# uven2-mk3-cc-interface.net
KiCad netlist of a schematic drawn in EasyEDA Pro
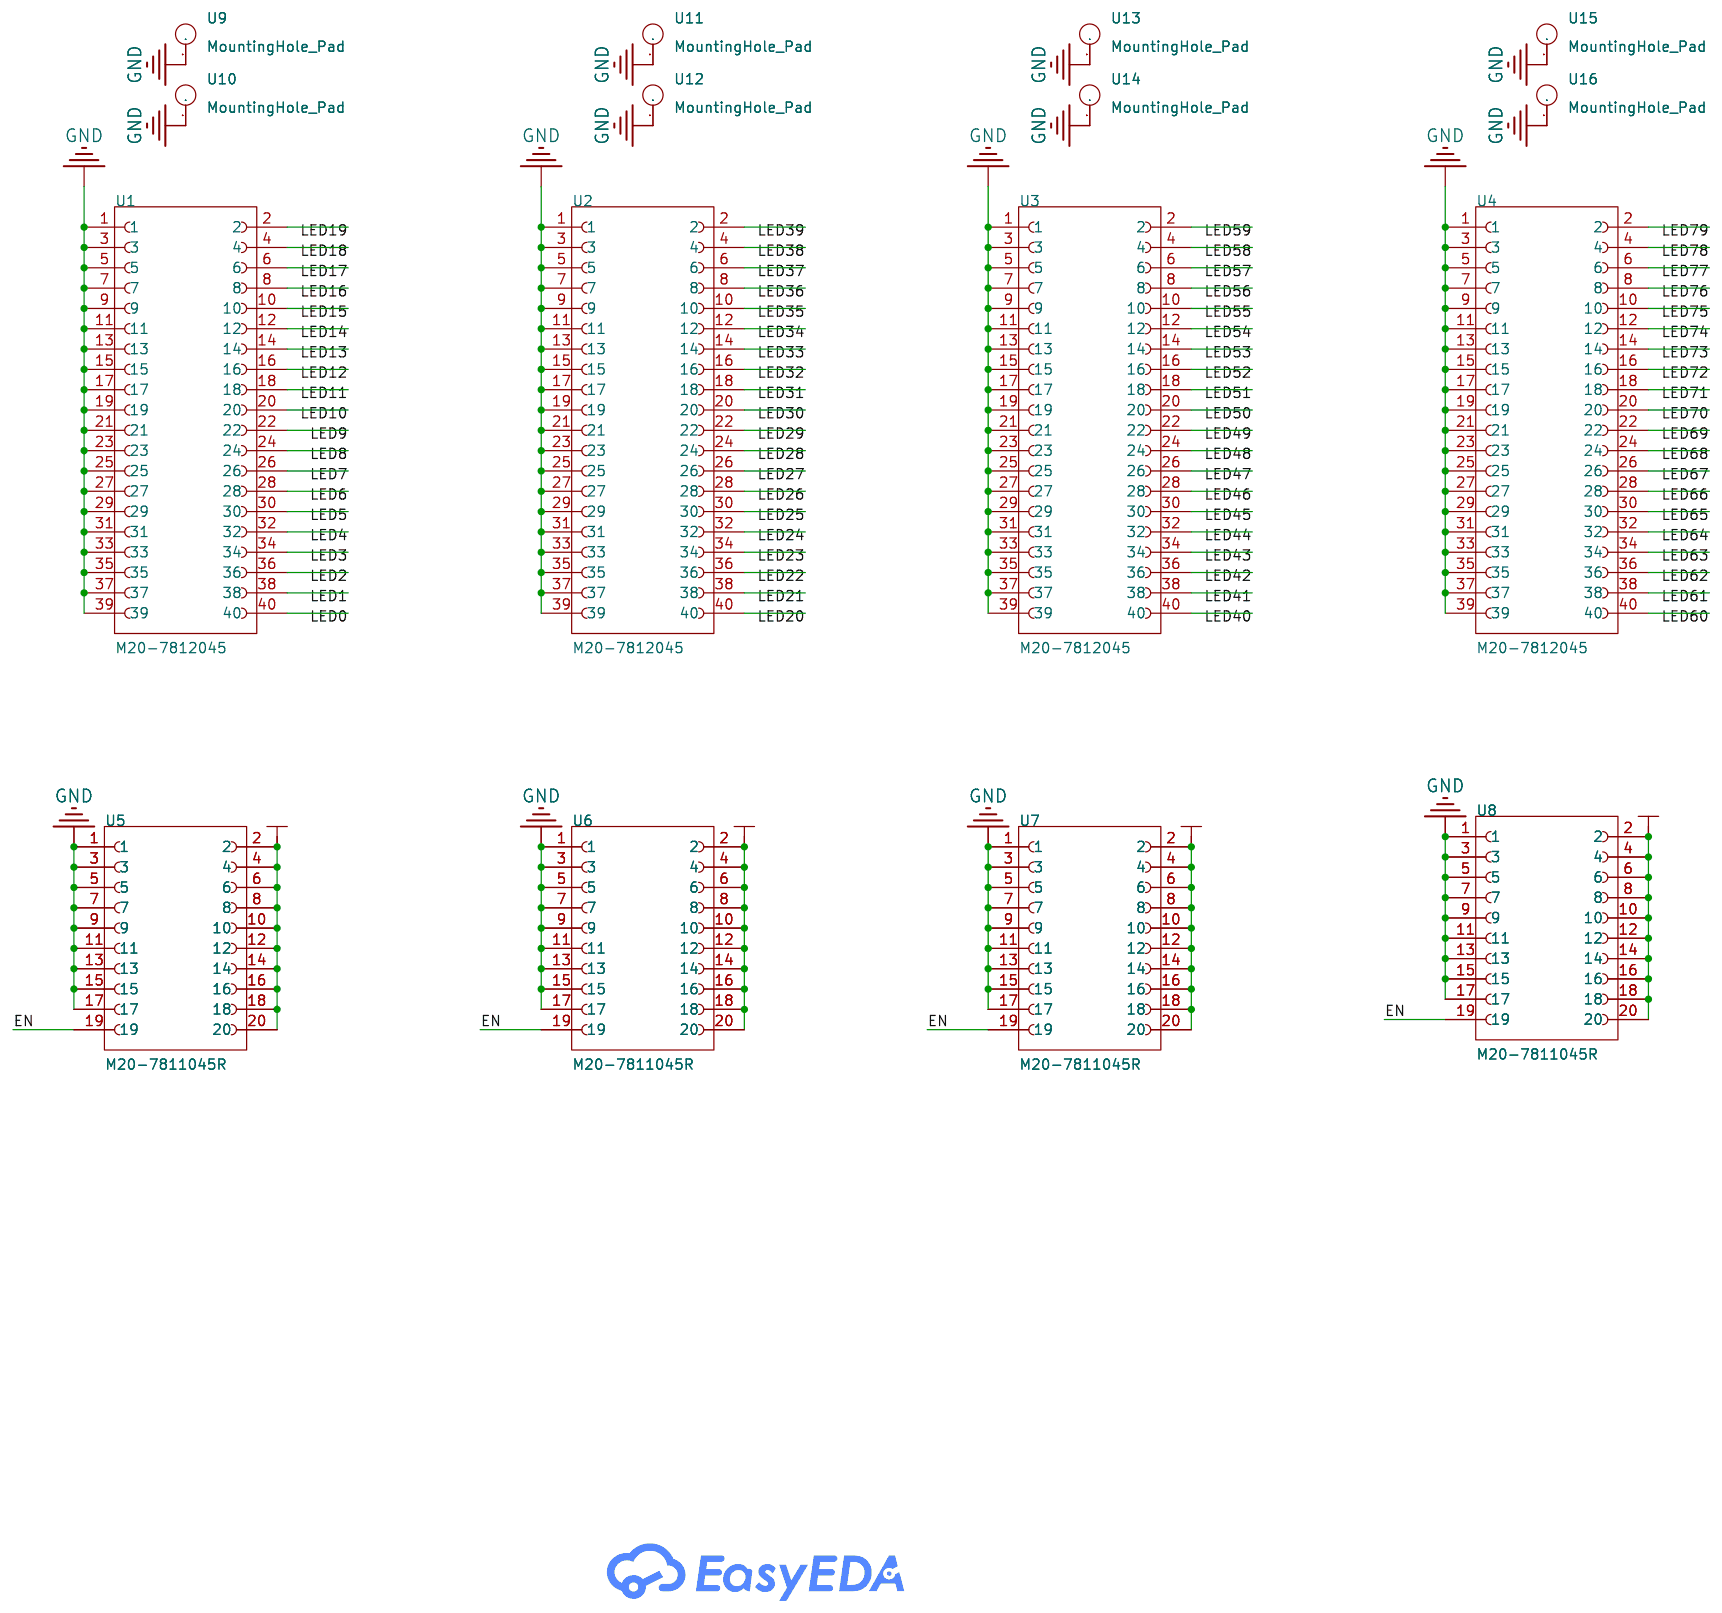
[diagram p0: schematic sheet]

(export (version "E")
  (design (tool "Eeschema 10.0.6"))
  (components
    (comp (ref "U1")
      (value "M20-7812045")
      (footprint "easyedapro:HARWIN_M20-7812045")
      (libsource (lib "easyedapro") (part "M20-7812045"))
    )
    (comp (ref "U2")
      (value "M20-7812045")
      (footprint "easyedapro:HARWIN_M20-7812045")
      (libsource (lib "easyedapro") (part "M20-7812045"))
    )
    (comp (ref "U3")
      (value "M20-7812045")
      (footprint "easyedapro:HARWIN_M20-7812045")
      (libsource (lib "easyedapro") (part "M20-7812045"))
    )
    (comp (ref "U4")
      (value "M20-7812045")
      (footprint "easyedapro:HARWIN_M20-7812045")
      (libsource (lib "easyedapro") (part "M20-7812045"))
    )
    (comp (ref "U5")
      (value "M20-7811045R")
      (footprint "easyedapro:HARWIN_M20-7811045R")
      (libsource (lib "easyedapro") (part "M20-7811045R"))
    )
    (comp (ref "U6")
      (value "M20-7811045R")
      (footprint "easyedapro:HARWIN_M20-7811045R")
      (libsource (lib "easyedapro") (part "M20-7811045R"))
    )
    (comp (ref "U7")
      (value "M20-7811045R")
      (footprint "easyedapro:HARWIN_M20-7811045R")
      (libsource (lib "easyedapro") (part "M20-7811045R"))
    )
    (comp (ref "U8")
      (value "M20-7811045R")
      (footprint "easyedapro:HARWIN_M20-7811045R")
      (libsource (lib "easyedapro") (part "M20-7811045R"))
    )
    (comp (ref "U9")
      (value "MountingHole_Pad")
      (footprint "easyedapro:MountingHole_3.2mm_M3_DIN965_Pad_TopOnly")
      (libsource (lib "easyedapro") (part "MountingHole_Pad"))
    )
    (comp (ref "U10")
      (value "MountingHole_Pad")
      (footprint "easyedapro:MountingHole_3.2mm_M3_DIN965_Pad_TopOnly")
      (libsource (lib "easyedapro") (part "MountingHole_Pad"))
    )
    (comp (ref "U11")
      (value "MountingHole_Pad")
      (footprint "easyedapro:MountingHole_3.2mm_M3_DIN965_Pad_TopOnly")
      (libsource (lib "easyedapro") (part "MountingHole_Pad"))
    )
    (comp (ref "U12")
      (value "MountingHole_Pad")
      (footprint "easyedapro:MountingHole_3.2mm_M3_DIN965_Pad_TopOnly")
      (libsource (lib "easyedapro") (part "MountingHole_Pad"))
    )
    (comp (ref "U13")
      (value "MountingHole_Pad")
      (footprint "easyedapro:MountingHole_3.2mm_M3_DIN965_Pad_TopOnly")
      (libsource (lib "easyedapro") (part "MountingHole_Pad"))
    )
    (comp (ref "U14")
      (value "MountingHole_Pad")
      (footprint "easyedapro:MountingHole_3.2mm_M3_DIN965_Pad_TopOnly")
      (libsource (lib "easyedapro") (part "MountingHole_Pad"))
    )
    (comp (ref "U15")
      (value "MountingHole_Pad")
      (footprint "easyedapro:MountingHole_3.2mm_M3_DIN965_Pad_TopOnly")
      (libsource (lib "easyedapro") (part "MountingHole_Pad"))
    )
    (comp (ref "U16")
      (value "MountingHole_Pad")
      (footprint "easyedapro:MountingHole_3.2mm_M3_DIN965_Pad_TopOnly")
      (libsource (lib "easyedapro") (part "MountingHole_Pad"))
    )
  )
  (nets
    (net (code "1") (name "+12V") (class "Default")
      (node (ref "U5") (pin "10") (pinfunction "10_10") (pintype "unspecified"))
      (node (ref "U5") (pin "12") (pinfunction "12_12") (pintype "unspecified"))
      (node (ref "U5") (pin "14") (pinfunction "14_14") (pintype "unspecified"))
      (node (ref "U5") (pin "16") (pinfunction "16_16") (pintype "unspecified"))
      (node (ref "U5") (pin "18") (pinfunction "18_18") (pintype "unspecified"))
      (node (ref "U5") (pin "2") (pinfunction "2_2") (pintype "unspecified"))
      (node (ref "U5") (pin "20") (pinfunction "20_20") (pintype "unspecified"))
      (node (ref "U5") (pin "4") (pinfunction "4_4") (pintype "unspecified"))
      (node (ref "U5") (pin "6") (pinfunction "6_6") (pintype "unspecified"))
      (node (ref "U5") (pin "8") (pinfunction "8_8") (pintype "unspecified"))
      (node (ref "U6") (pin "10") (pinfunction "10_10") (pintype "unspecified"))
      (node (ref "U6") (pin "12") (pinfunction "12_12") (pintype "unspecified"))
      (node (ref "U6") (pin "14") (pinfunction "14_14") (pintype "unspecified"))
      (node (ref "U6") (pin "16") (pinfunction "16_16") (pintype "unspecified"))
      (node (ref "U6") (pin "18") (pinfunction "18_18") (pintype "unspecified"))
      (node (ref "U6") (pin "2") (pinfunction "2_2") (pintype "unspecified"))
      (node (ref "U6") (pin "20") (pinfunction "20_20") (pintype "unspecified"))
      (node (ref "U6") (pin "4") (pinfunction "4_4") (pintype "unspecified"))
      (node (ref "U6") (pin "6") (pinfunction "6_6") (pintype "unspecified"))
      (node (ref "U6") (pin "8") (pinfunction "8_8") (pintype "unspecified"))
      (node (ref "U7") (pin "10") (pinfunction "10_10") (pintype "unspecified"))
      (node (ref "U7") (pin "12") (pinfunction "12_12") (pintype "unspecified"))
      (node (ref "U7") (pin "14") (pinfunction "14_14") (pintype "unspecified"))
      (node (ref "U7") (pin "16") (pinfunction "16_16") (pintype "unspecified"))
      (node (ref "U7") (pin "18") (pinfunction "18_18") (pintype "unspecified"))
      (node (ref "U7") (pin "2") (pinfunction "2_2") (pintype "unspecified"))
      (node (ref "U7") (pin "20") (pinfunction "20_20") (pintype "unspecified"))
      (node (ref "U7") (pin "4") (pinfunction "4_4") (pintype "unspecified"))
      (node (ref "U7") (pin "6") (pinfunction "6_6") (pintype "unspecified"))
      (node (ref "U7") (pin "8") (pinfunction "8_8") (pintype "unspecified"))
      (node (ref "U8") (pin "10") (pinfunction "10_10") (pintype "unspecified"))
      (node (ref "U8") (pin "12") (pinfunction "12_12") (pintype "unspecified"))
      (node (ref "U8") (pin "14") (pinfunction "14_14") (pintype "unspecified"))
      (node (ref "U8") (pin "16") (pinfunction "16_16") (pintype "unspecified"))
      (node (ref "U8") (pin "18") (pinfunction "18_18") (pintype "unspecified"))
      (node (ref "U8") (pin "2") (pinfunction "2_2") (pintype "unspecified"))
      (node (ref "U8") (pin "20") (pinfunction "20_20") (pintype "unspecified"))
      (node (ref "U8") (pin "4") (pinfunction "4_4") (pintype "unspecified"))
      (node (ref "U8") (pin "6") (pinfunction "6_6") (pintype "unspecified"))
      (node (ref "U8") (pin "8") (pinfunction "8_8") (pintype "unspecified"))
    )
    (net (code "2") (name "/EN") (class "Default")
      (node (ref "U5") (pin "19") (pinfunction "19_19") (pintype "unspecified"))
      (node (ref "U6") (pin "19") (pinfunction "19_19") (pintype "unspecified"))
      (node (ref "U7") (pin "19") (pinfunction "19_19") (pintype "unspecified"))
      (node (ref "U8") (pin "19") (pinfunction "19_19") (pintype "unspecified"))
    )
    (net (code "3") (name "/LED0") (class "Default")
      (node (ref "U1") (pin "40") (pinfunction "40_40") (pintype "unspecified"))
    )
    (net (code "4") (name "/LED1") (class "Default")
      (node (ref "U1") (pin "38") (pinfunction "38_38") (pintype "unspecified"))
    )
    (net (code "5") (name "/LED2") (class "Default")
      (node (ref "U1") (pin "36") (pinfunction "36_36") (pintype "unspecified"))
    )
    (net (code "6") (name "/LED3") (class "Default")
      (node (ref "U1") (pin "34") (pinfunction "34_34") (pintype "unspecified"))
    )
    (net (code "7") (name "/LED4") (class "Default")
      (node (ref "U1") (pin "32") (pinfunction "32_32") (pintype "unspecified"))
    )
    (net (code "8") (name "/LED5") (class "Default")
      (node (ref "U1") (pin "30") (pinfunction "30_30") (pintype "unspecified"))
    )
    (net (code "9") (name "/LED6") (class "Default")
      (node (ref "U1") (pin "28") (pinfunction "28_28") (pintype "unspecified"))
    )
    (net (code "10") (name "/LED7") (class "Default")
      (node (ref "U1") (pin "26") (pinfunction "26_26") (pintype "unspecified"))
    )
    (net (code "11") (name "/LED8") (class "Default")
      (node (ref "U1") (pin "24") (pinfunction "24_24") (pintype "unspecified"))
    )
    (net (code "12") (name "/LED9") (class "Default")
      (node (ref "U1") (pin "22") (pinfunction "22_22") (pintype "unspecified"))
    )
    (net (code "13") (name "/LED10") (class "Default")
      (node (ref "U1") (pin "20") (pinfunction "20_20") (pintype "unspecified"))
    )
    (net (code "14") (name "/LED11") (class "Default")
      (node (ref "U1") (pin "18") (pinfunction "18_18") (pintype "unspecified"))
    )
    (net (code "15") (name "/LED12") (class "Default")
      (node (ref "U1") (pin "16") (pinfunction "16_16") (pintype "unspecified"))
    )
    (net (code "16") (name "/LED13") (class "Default")
      (node (ref "U1") (pin "14") (pinfunction "14_14") (pintype "unspecified"))
    )
    (net (code "17") (name "/LED14") (class "Default")
      (node (ref "U1") (pin "12") (pinfunction "12_12") (pintype "unspecified"))
    )
    (net (code "18") (name "/LED15") (class "Default")
      (node (ref "U1") (pin "10") (pinfunction "10_10") (pintype "unspecified"))
    )
    (net (code "19") (name "/LED16") (class "Default")
      (node (ref "U1") (pin "8") (pinfunction "8_8") (pintype "unspecified"))
    )
    (net (code "20") (name "/LED17") (class "Default")
      (node (ref "U1") (pin "6") (pinfunction "6_6") (pintype "unspecified"))
    )
    (net (code "21") (name "/LED18") (class "Default")
      (node (ref "U1") (pin "4") (pinfunction "4_4") (pintype "unspecified"))
    )
    (net (code "22") (name "/LED19") (class "Default")
      (node (ref "U1") (pin "2") (pinfunction "2_2") (pintype "unspecified"))
    )
    (net (code "23") (name "/LED20") (class "Default")
      (node (ref "U2") (pin "40") (pinfunction "40_40") (pintype "unspecified"))
    )
    (net (code "24") (name "/LED21") (class "Default")
      (node (ref "U2") (pin "38") (pinfunction "38_38") (pintype "unspecified"))
    )
    (net (code "25") (name "/LED22") (class "Default")
      (node (ref "U2") (pin "36") (pinfunction "36_36") (pintype "unspecified"))
    )
    (net (code "26") (name "/LED23") (class "Default")
      (node (ref "U2") (pin "34") (pinfunction "34_34") (pintype "unspecified"))
    )
    (net (code "27") (name "/LED24") (class "Default")
      (node (ref "U2") (pin "32") (pinfunction "32_32") (pintype "unspecified"))
    )
    (net (code "28") (name "/LED25") (class "Default")
      (node (ref "U2") (pin "30") (pinfunction "30_30") (pintype "unspecified"))
    )
    (net (code "29") (name "/LED26") (class "Default")
      (node (ref "U2") (pin "28") (pinfunction "28_28") (pintype "unspecified"))
    )
    (net (code "30") (name "/LED27") (class "Default")
      (node (ref "U2") (pin "26") (pinfunction "26_26") (pintype "unspecified"))
    )
    (net (code "31") (name "/LED28") (class "Default")
      (node (ref "U2") (pin "24") (pinfunction "24_24") (pintype "unspecified"))
    )
    (net (code "32") (name "/LED29") (class "Default")
      (node (ref "U2") (pin "22") (pinfunction "22_22") (pintype "unspecified"))
    )
    (net (code "33") (name "/LED30") (class "Default")
      (node (ref "U2") (pin "20") (pinfunction "20_20") (pintype "unspecified"))
    )
    (net (code "34") (name "/LED31") (class "Default")
      (node (ref "U2") (pin "18") (pinfunction "18_18") (pintype "unspecified"))
    )
    (net (code "35") (name "/LED32") (class "Default")
      (node (ref "U2") (pin "16") (pinfunction "16_16") (pintype "unspecified"))
    )
    (net (code "36") (name "/LED33") (class "Default")
      (node (ref "U2") (pin "14") (pinfunction "14_14") (pintype "unspecified"))
    )
    (net (code "37") (name "/LED34") (class "Default")
      (node (ref "U2") (pin "12") (pinfunction "12_12") (pintype "unspecified"))
    )
    (net (code "38") (name "/LED35") (class "Default")
      (node (ref "U2") (pin "10") (pinfunction "10_10") (pintype "unspecified"))
    )
    (net (code "39") (name "/LED36") (class "Default")
      (node (ref "U2") (pin "8") (pinfunction "8_8") (pintype "unspecified"))
    )
    (net (code "40") (name "/LED37") (class "Default")
      (node (ref "U2") (pin "6") (pinfunction "6_6") (pintype "unspecified"))
    )
    (net (code "41") (name "/LED38") (class "Default")
      (node (ref "U2") (pin "4") (pinfunction "4_4") (pintype "unspecified"))
    )
    (net (code "42") (name "/LED39") (class "Default")
      (node (ref "U2") (pin "2") (pinfunction "2_2") (pintype "unspecified"))
    )
    (net (code "43") (name "/LED40") (class "Default")
      (node (ref "U3") (pin "40") (pinfunction "40_40") (pintype "unspecified"))
    )
    (net (code "44") (name "/LED41") (class "Default")
      (node (ref "U3") (pin "38") (pinfunction "38_38") (pintype "unspecified"))
    )
    (net (code "45") (name "/LED42") (class "Default")
      (node (ref "U3") (pin "36") (pinfunction "36_36") (pintype "unspecified"))
    )
    (net (code "46") (name "/LED43") (class "Default")
      (node (ref "U3") (pin "34") (pinfunction "34_34") (pintype "unspecified"))
    )
    (net (code "47") (name "/LED44") (class "Default")
      (node (ref "U3") (pin "32") (pinfunction "32_32") (pintype "unspecified"))
    )
    (net (code "48") (name "/LED45") (class "Default")
      (node (ref "U3") (pin "30") (pinfunction "30_30") (pintype "unspecified"))
    )
    (net (code "49") (name "/LED46") (class "Default")
      (node (ref "U3") (pin "28") (pinfunction "28_28") (pintype "unspecified"))
    )
    (net (code "50") (name "/LED47") (class "Default")
      (node (ref "U3") (pin "26") (pinfunction "26_26") (pintype "unspecified"))
    )
    (net (code "51") (name "/LED48") (class "Default")
      (node (ref "U3") (pin "24") (pinfunction "24_24") (pintype "unspecified"))
    )
    (net (code "52") (name "/LED49") (class "Default")
      (node (ref "U3") (pin "22") (pinfunction "22_22") (pintype "unspecified"))
    )
    (net (code "53") (name "/LED50") (class "Default")
      (node (ref "U3") (pin "20") (pinfunction "20_20") (pintype "unspecified"))
    )
    (net (code "54") (name "/LED51") (class "Default")
      (node (ref "U3") (pin "18") (pinfunction "18_18") (pintype "unspecified"))
    )
    (net (code "55") (name "/LED52") (class "Default")
      (node (ref "U3") (pin "16") (pinfunction "16_16") (pintype "unspecified"))
    )
    (net (code "56") (name "/LED53") (class "Default")
      (node (ref "U3") (pin "14") (pinfunction "14_14") (pintype "unspecified"))
    )
    (net (code "57") (name "/LED54") (class "Default")
      (node (ref "U3") (pin "12") (pinfunction "12_12") (pintype "unspecified"))
    )
    (net (code "58") (name "/LED55") (class "Default")
      (node (ref "U3") (pin "10") (pinfunction "10_10") (pintype "unspecified"))
    )
    (net (code "59") (name "/LED56") (class "Default")
      (node (ref "U3") (pin "8") (pinfunction "8_8") (pintype "unspecified"))
    )
    (net (code "60") (name "/LED57") (class "Default")
      (node (ref "U3") (pin "6") (pinfunction "6_6") (pintype "unspecified"))
    )
    (net (code "61") (name "/LED58") (class "Default")
      (node (ref "U3") (pin "4") (pinfunction "4_4") (pintype "unspecified"))
    )
    (net (code "62") (name "/LED59") (class "Default")
      (node (ref "U3") (pin "2") (pinfunction "2_2") (pintype "unspecified"))
    )
    (net (code "63") (name "/LED60") (class "Default")
      (node (ref "U4") (pin "40") (pinfunction "40_40") (pintype "unspecified"))
    )
    (net (code "64") (name "/LED61") (class "Default")
      (node (ref "U4") (pin "38") (pinfunction "38_38") (pintype "unspecified"))
    )
    (net (code "65") (name "/LED62") (class "Default")
      (node (ref "U4") (pin "36") (pinfunction "36_36") (pintype "unspecified"))
    )
    (net (code "66") (name "/LED63") (class "Default")
      (node (ref "U4") (pin "34") (pinfunction "34_34") (pintype "unspecified"))
    )
    (net (code "67") (name "/LED64") (class "Default")
      (node (ref "U4") (pin "32") (pinfunction "32_32") (pintype "unspecified"))
    )
    (net (code "68") (name "/LED65") (class "Default")
      (node (ref "U4") (pin "30") (pinfunction "30_30") (pintype "unspecified"))
    )
    (net (code "69") (name "/LED66") (class "Default")
      (node (ref "U4") (pin "28") (pinfunction "28_28") (pintype "unspecified"))
    )
    (net (code "70") (name "/LED67") (class "Default")
      (node (ref "U4") (pin "26") (pinfunction "26_26") (pintype "unspecified"))
    )
    (net (code "71") (name "/LED68") (class "Default")
      (node (ref "U4") (pin "24") (pinfunction "24_24") (pintype "unspecified"))
    )
    (net (code "72") (name "/LED69") (class "Default")
      (node (ref "U4") (pin "22") (pinfunction "22_22") (pintype "unspecified"))
    )
    (net (code "73") (name "/LED70") (class "Default")
      (node (ref "U4") (pin "20") (pinfunction "20_20") (pintype "unspecified"))
    )
    (net (code "74") (name "/LED71") (class "Default")
      (node (ref "U4") (pin "18") (pinfunction "18_18") (pintype "unspecified"))
    )
    (net (code "75") (name "/LED72") (class "Default")
      (node (ref "U4") (pin "16") (pinfunction "16_16") (pintype "unspecified"))
    )
    (net (code "76") (name "/LED73") (class "Default")
      (node (ref "U4") (pin "14") (pinfunction "14_14") (pintype "unspecified"))
    )
    (net (code "77") (name "/LED74") (class "Default")
      (node (ref "U4") (pin "12") (pinfunction "12_12") (pintype "unspecified"))
    )
    (net (code "78") (name "/LED75") (class "Default")
      (node (ref "U4") (pin "10") (pinfunction "10_10") (pintype "unspecified"))
    )
    (net (code "79") (name "/LED76") (class "Default")
      (node (ref "U4") (pin "8") (pinfunction "8_8") (pintype "unspecified"))
    )
    (net (code "80") (name "/LED77") (class "Default")
      (node (ref "U4") (pin "6") (pinfunction "6_6") (pintype "unspecified"))
    )
    (net (code "81") (name "/LED78") (class "Default")
      (node (ref "U4") (pin "4") (pinfunction "4_4") (pintype "unspecified"))
    )
    (net (code "82") (name "/LED79") (class "Default")
      (node (ref "U4") (pin "2") (pinfunction "2_2") (pintype "unspecified"))
    )
    (net (code "83") (name "GND") (class "Default")
      (node (ref "U1") (pin "1") (pinfunction "1_1") (pintype "unspecified"))
      (node (ref "U1") (pin "11") (pinfunction "11_11") (pintype "unspecified"))
      (node (ref "U1") (pin "13") (pinfunction "13_13") (pintype "unspecified"))
      (node (ref "U1") (pin "15") (pinfunction "15_15") (pintype "unspecified"))
      (node (ref "U1") (pin "17") (pinfunction "17_17") (pintype "unspecified"))
      (node (ref "U1") (pin "19") (pinfunction "19_19") (pintype "unspecified"))
      (node (ref "U1") (pin "21") (pinfunction "21_21") (pintype "unspecified"))
      (node (ref "U1") (pin "23") (pinfunction "23_23") (pintype "unspecified"))
      (node (ref "U1") (pin "25") (pinfunction "25_25") (pintype "unspecified"))
      (node (ref "U1") (pin "27") (pinfunction "27_27") (pintype "unspecified"))
      (node (ref "U1") (pin "29") (pinfunction "29_29") (pintype "unspecified"))
      (node (ref "U1") (pin "3") (pinfunction "3_3") (pintype "unspecified"))
      (node (ref "U1") (pin "31") (pinfunction "31_31") (pintype "unspecified"))
      (node (ref "U1") (pin "33") (pinfunction "33_33") (pintype "unspecified"))
      (node (ref "U1") (pin "35") (pinfunction "35_35") (pintype "unspecified"))
      (node (ref "U1") (pin "37") (pinfunction "37_37") (pintype "unspecified"))
      (node (ref "U1") (pin "39") (pinfunction "39_39") (pintype "unspecified"))
      (node (ref "U1") (pin "5") (pinfunction "5_5") (pintype "unspecified"))
      (node (ref "U1") (pin "7") (pinfunction "7_7") (pintype "unspecified"))
      (node (ref "U1") (pin "9") (pinfunction "9_9") (pintype "unspecified"))
      (node (ref "U10") (pin "1") (pinfunction "1_1") (pintype "input"))
      (node (ref "U11") (pin "1") (pinfunction "1_1") (pintype "input"))
      (node (ref "U12") (pin "1") (pinfunction "1_1") (pintype "input"))
      (node (ref "U13") (pin "1") (pinfunction "1_1") (pintype "input"))
      (node (ref "U14") (pin "1") (pinfunction "1_1") (pintype "input"))
      (node (ref "U15") (pin "1") (pinfunction "1_1") (pintype "input"))
      (node (ref "U16") (pin "1") (pinfunction "1_1") (pintype "input"))
      (node (ref "U2") (pin "1") (pinfunction "1_1") (pintype "unspecified"))
      (node (ref "U2") (pin "11") (pinfunction "11_11") (pintype "unspecified"))
      (node (ref "U2") (pin "13") (pinfunction "13_13") (pintype "unspecified"))
      (node (ref "U2") (pin "15") (pinfunction "15_15") (pintype "unspecified"))
      (node (ref "U2") (pin "17") (pinfunction "17_17") (pintype "unspecified"))
      (node (ref "U2") (pin "19") (pinfunction "19_19") (pintype "unspecified"))
      (node (ref "U2") (pin "21") (pinfunction "21_21") (pintype "unspecified"))
      (node (ref "U2") (pin "23") (pinfunction "23_23") (pintype "unspecified"))
      (node (ref "U2") (pin "25") (pinfunction "25_25") (pintype "unspecified"))
      (node (ref "U2") (pin "27") (pinfunction "27_27") (pintype "unspecified"))
      (node (ref "U2") (pin "29") (pinfunction "29_29") (pintype "unspecified"))
      (node (ref "U2") (pin "3") (pinfunction "3_3") (pintype "unspecified"))
      (node (ref "U2") (pin "31") (pinfunction "31_31") (pintype "unspecified"))
      (node (ref "U2") (pin "33") (pinfunction "33_33") (pintype "unspecified"))
      (node (ref "U2") (pin "35") (pinfunction "35_35") (pintype "unspecified"))
      (node (ref "U2") (pin "37") (pinfunction "37_37") (pintype "unspecified"))
      (node (ref "U2") (pin "39") (pinfunction "39_39") (pintype "unspecified"))
      (node (ref "U2") (pin "5") (pinfunction "5_5") (pintype "unspecified"))
      (node (ref "U2") (pin "7") (pinfunction "7_7") (pintype "unspecified"))
      (node (ref "U2") (pin "9") (pinfunction "9_9") (pintype "unspecified"))
      (node (ref "U3") (pin "1") (pinfunction "1_1") (pintype "unspecified"))
      (node (ref "U3") (pin "11") (pinfunction "11_11") (pintype "unspecified"))
      (node (ref "U3") (pin "13") (pinfunction "13_13") (pintype "unspecified"))
      (node (ref "U3") (pin "15") (pinfunction "15_15") (pintype "unspecified"))
      (node (ref "U3") (pin "17") (pinfunction "17_17") (pintype "unspecified"))
      (node (ref "U3") (pin "19") (pinfunction "19_19") (pintype "unspecified"))
      (node (ref "U3") (pin "21") (pinfunction "21_21") (pintype "unspecified"))
      (node (ref "U3") (pin "23") (pinfunction "23_23") (pintype "unspecified"))
      (node (ref "U3") (pin "25") (pinfunction "25_25") (pintype "unspecified"))
      (node (ref "U3") (pin "27") (pinfunction "27_27") (pintype "unspecified"))
      (node (ref "U3") (pin "29") (pinfunction "29_29") (pintype "unspecified"))
      (node (ref "U3") (pin "3") (pinfunction "3_3") (pintype "unspecified"))
      (node (ref "U3") (pin "31") (pinfunction "31_31") (pintype "unspecified"))
      (node (ref "U3") (pin "33") (pinfunction "33_33") (pintype "unspecified"))
      (node (ref "U3") (pin "35") (pinfunction "35_35") (pintype "unspecified"))
      (node (ref "U3") (pin "37") (pinfunction "37_37") (pintype "unspecified"))
      (node (ref "U3") (pin "39") (pinfunction "39_39") (pintype "unspecified"))
      (node (ref "U3") (pin "5") (pinfunction "5_5") (pintype "unspecified"))
      (node (ref "U3") (pin "7") (pinfunction "7_7") (pintype "unspecified"))
      (node (ref "U3") (pin "9") (pinfunction "9_9") (pintype "unspecified"))
      (node (ref "U4") (pin "1") (pinfunction "1_1") (pintype "unspecified"))
      (node (ref "U4") (pin "11") (pinfunction "11_11") (pintype "unspecified"))
      (node (ref "U4") (pin "13") (pinfunction "13_13") (pintype "unspecified"))
      (node (ref "U4") (pin "15") (pinfunction "15_15") (pintype "unspecified"))
      (node (ref "U4") (pin "17") (pinfunction "17_17") (pintype "unspecified"))
      (node (ref "U4") (pin "19") (pinfunction "19_19") (pintype "unspecified"))
      (node (ref "U4") (pin "21") (pinfunction "21_21") (pintype "unspecified"))
      (node (ref "U4") (pin "23") (pinfunction "23_23") (pintype "unspecified"))
      (node (ref "U4") (pin "25") (pinfunction "25_25") (pintype "unspecified"))
      (node (ref "U4") (pin "27") (pinfunction "27_27") (pintype "unspecified"))
      (node (ref "U4") (pin "29") (pinfunction "29_29") (pintype "unspecified"))
      (node (ref "U4") (pin "3") (pinfunction "3_3") (pintype "unspecified"))
      (node (ref "U4") (pin "31") (pinfunction "31_31") (pintype "unspecified"))
      (node (ref "U4") (pin "33") (pinfunction "33_33") (pintype "unspecified"))
      (node (ref "U4") (pin "35") (pinfunction "35_35") (pintype "unspecified"))
      (node (ref "U4") (pin "37") (pinfunction "37_37") (pintype "unspecified"))
      (node (ref "U4") (pin "39") (pinfunction "39_39") (pintype "unspecified"))
      (node (ref "U4") (pin "5") (pinfunction "5_5") (pintype "unspecified"))
      (node (ref "U4") (pin "7") (pinfunction "7_7") (pintype "unspecified"))
      (node (ref "U4") (pin "9") (pinfunction "9_9") (pintype "unspecified"))
      (node (ref "U5") (pin "1") (pinfunction "1_1") (pintype "unspecified"))
      (node (ref "U5") (pin "11") (pinfunction "11_11") (pintype "unspecified"))
      (node (ref "U5") (pin "13") (pinfunction "13_13") (pintype "unspecified"))
      (node (ref "U5") (pin "15") (pinfunction "15_15") (pintype "unspecified"))
      (node (ref "U5") (pin "17") (pinfunction "17_17") (pintype "unspecified"))
      (node (ref "U5") (pin "3") (pinfunction "3_3") (pintype "unspecified"))
      (node (ref "U5") (pin "5") (pinfunction "5_5") (pintype "unspecified"))
      (node (ref "U5") (pin "7") (pinfunction "7_7") (pintype "unspecified"))
      (node (ref "U5") (pin "9") (pinfunction "9_9") (pintype "unspecified"))
      (node (ref "U6") (pin "1") (pinfunction "1_1") (pintype "unspecified"))
      (node (ref "U6") (pin "11") (pinfunction "11_11") (pintype "unspecified"))
      (node (ref "U6") (pin "13") (pinfunction "13_13") (pintype "unspecified"))
      (node (ref "U6") (pin "15") (pinfunction "15_15") (pintype "unspecified"))
      (node (ref "U6") (pin "17") (pinfunction "17_17") (pintype "unspecified"))
      (node (ref "U6") (pin "3") (pinfunction "3_3") (pintype "unspecified"))
      (node (ref "U6") (pin "5") (pinfunction "5_5") (pintype "unspecified"))
      (node (ref "U6") (pin "7") (pinfunction "7_7") (pintype "unspecified"))
      (node (ref "U6") (pin "9") (pinfunction "9_9") (pintype "unspecified"))
      (node (ref "U7") (pin "1") (pinfunction "1_1") (pintype "unspecified"))
      (node (ref "U7") (pin "11") (pinfunction "11_11") (pintype "unspecified"))
      (node (ref "U7") (pin "13") (pinfunction "13_13") (pintype "unspecified"))
      (node (ref "U7") (pin "15") (pinfunction "15_15") (pintype "unspecified"))
      (node (ref "U7") (pin "17") (pinfunction "17_17") (pintype "unspecified"))
      (node (ref "U7") (pin "3") (pinfunction "3_3") (pintype "unspecified"))
      (node (ref "U7") (pin "5") (pinfunction "5_5") (pintype "unspecified"))
      (node (ref "U7") (pin "7") (pinfunction "7_7") (pintype "unspecified"))
      (node (ref "U7") (pin "9") (pinfunction "9_9") (pintype "unspecified"))
      (node (ref "U8") (pin "1") (pinfunction "1_1") (pintype "unspecified"))
      (node (ref "U8") (pin "11") (pinfunction "11_11") (pintype "unspecified"))
      (node (ref "U8") (pin "13") (pinfunction "13_13") (pintype "unspecified"))
      (node (ref "U8") (pin "15") (pinfunction "15_15") (pintype "unspecified"))
      (node (ref "U8") (pin "17") (pinfunction "17_17") (pintype "unspecified"))
      (node (ref "U8") (pin "3") (pinfunction "3_3") (pintype "unspecified"))
      (node (ref "U8") (pin "5") (pinfunction "5_5") (pintype "unspecified"))
      (node (ref "U8") (pin "7") (pinfunction "7_7") (pintype "unspecified"))
      (node (ref "U8") (pin "9") (pinfunction "9_9") (pintype "unspecified"))
      (node (ref "U9") (pin "1") (pinfunction "1_1") (pintype "input"))
    )
  )
)
